# Non-Isolated_Interface.net
KiCad netlist of a schematic drawn in Altium Designer
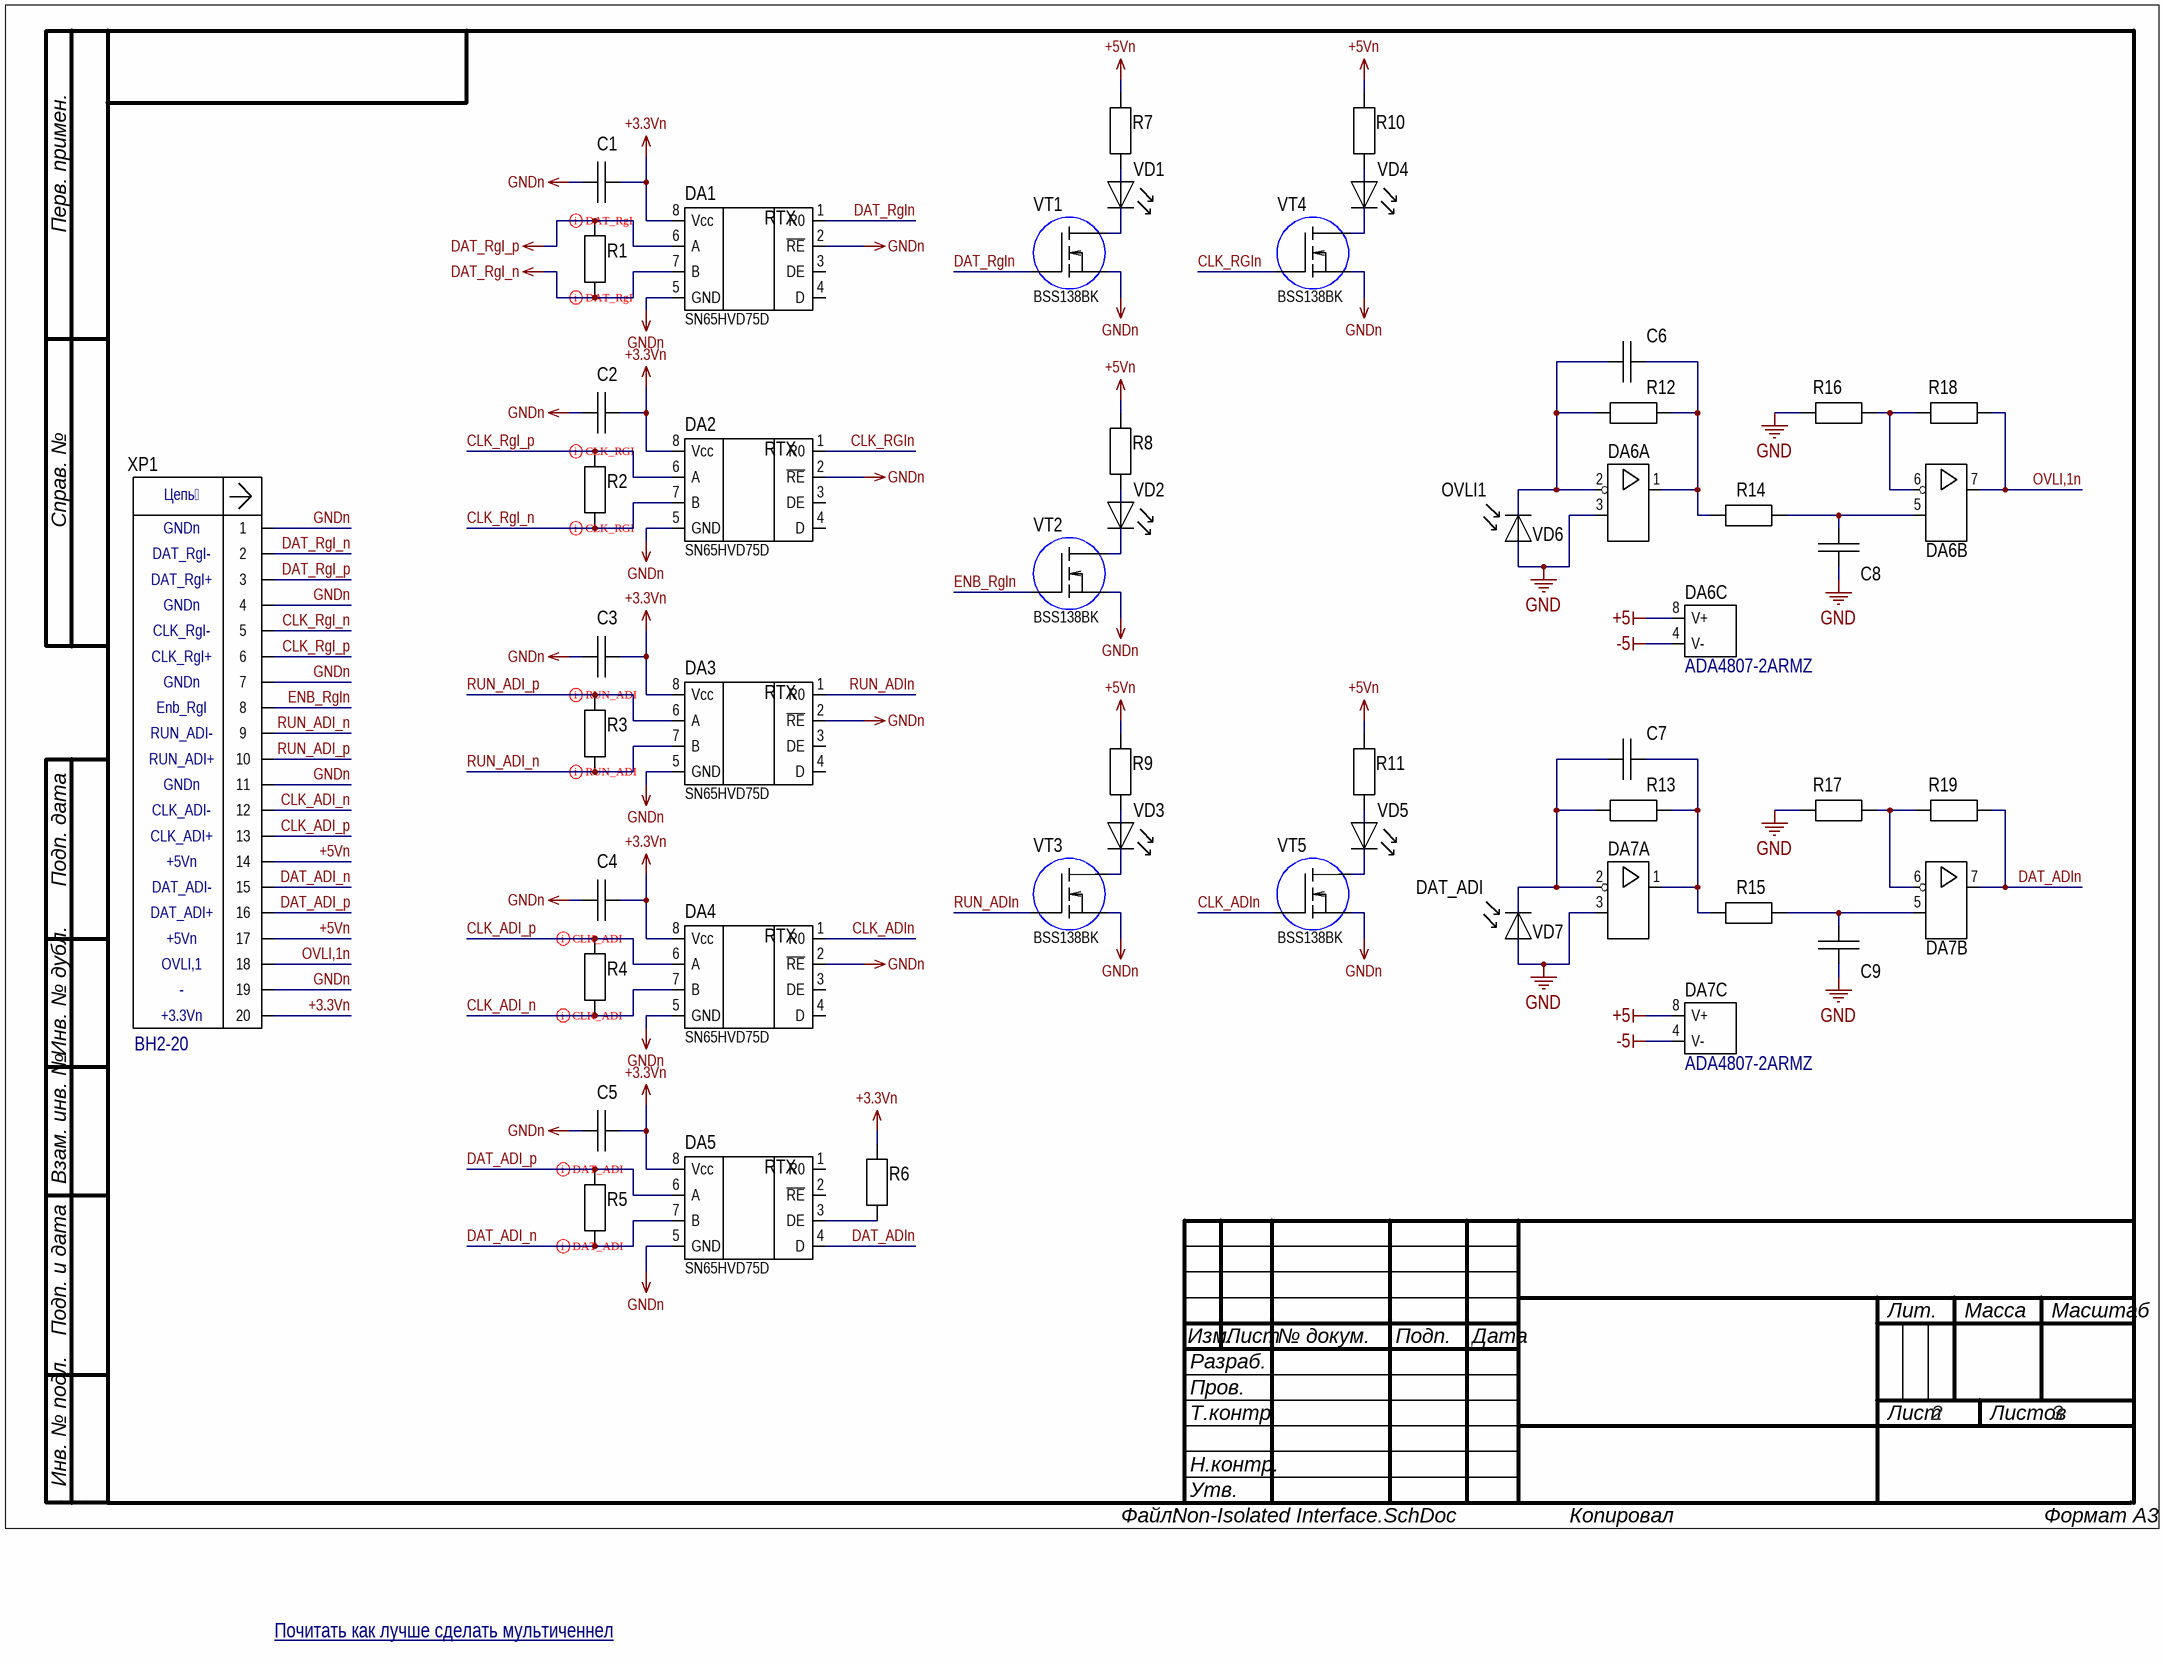
[diagram p0: Non-Isolated Interface.SchDoc]

(export (version "E")
  (design (tool "Eeschema 10.0.6"))
  (components
    (comp (ref "C1")
      (value "0805-X7R-25 В-0,1 мкФ +-10%")
      (footprint "standard-case:CAP: 0805")
      (libsource (lib "МНИПИ_Конденсаторы") (part "0805-X7R-25 В-0,1 мкФ +-10%"))
    )
    (comp (ref "C2")
      (value "0805-X7R-25 В-0,1 мкФ +-10%")
      (footprint "standard-case:CAP: 0805")
      (libsource (lib "МНИПИ_Конденсаторы") (part "0805-X7R-25 В-0,1 мкФ +-10%"))
    )
    (comp (ref "C3")
      (value "0805-X7R-25 В-0,1 мкФ +-10%")
      (footprint "standard-case:CAP: 0805")
      (libsource (lib "МНИПИ_Конденсаторы") (part "0805-X7R-25 В-0,1 мкФ +-10%"))
    )
    (comp (ref "C4")
      (value "0805-X7R-25 В-0,1 мкФ +-10%")
      (footprint "standard-case:CAP: 0805")
      (libsource (lib "МНИПИ_Конденсаторы") (part "0805-X7R-25 В-0,1 мкФ +-10%"))
    )
    (comp (ref "C5")
      (value "0805-X7R-25 В-0,1 мкФ +-10%")
      (footprint "standard-case:CAP: 0805")
      (libsource (lib "МНИПИ_Конденсаторы") (part "0805-X7R-25 В-0,1 мкФ +-10%"))
    )
    (comp (ref "C6")
      (value "0805-NP0-50 В-2,4 пФ-1%")
      (footprint "standard-case:CAP: 0805")
      (libsource (lib "МНИПИ_Конденсаторы") (part "0805-NP0-50 В-2,4 пФ-1%"))
    )
    (comp (ref "C7")
      (value "0805-NP0-50 В-2,4 пФ-1%")
      (footprint "standard-case:CAP: 0805")
      (libsource (lib "МНИПИ_Конденсаторы") (part "0805-NP0-50 В-2,4 пФ-1%"))
    )
    (comp (ref "C8")
      (value "1206-С0G-50 B-56 пФ+-1%")
      (footprint "standard-case:CAP: 1206")
      (libsource (lib "МНИПИ_Конденсаторы") (part "1206-С0G-50 B-56 пФ+-1%"))
    )
    (comp (ref "C9")
      (value "1206-С0G-50 B-56 пФ+-1%")
      (footprint "standard-case:CAP: 1206")
      (libsource (lib "МНИПИ_Конденсаторы") (part "1206-С0G-50 B-56 пФ+-1%"))
    )
    (comp (ref "DA1")
      (value "SN65HVD75D")
      (footprint "8-SOIC")
      (libsource (lib "МНИПИ_Микросхемы") (part "SN65HVD75D"))
    )
    (comp (ref "DA2")
      (value "SN65HVD75D")
      (footprint "8-SOIC")
      (libsource (lib "МНИПИ_Микросхемы") (part "SN65HVD75D"))
    )
    (comp (ref "DA3")
      (value "SN65HVD75D")
      (footprint "8-SOIC")
      (libsource (lib "МНИПИ_Микросхемы") (part "SN65HVD75D"))
    )
    (comp (ref "DA4")
      (value "SN65HVD75D")
      (footprint "8-SOIC")
      (libsource (lib "МНИПИ_Микросхемы") (part "SN65HVD75D"))
    )
    (comp (ref "DA5")
      (value "SN65HVD75D")
      (footprint "8-SOIC")
      (libsource (lib "МНИПИ_Микросхемы") (part "SN65HVD75D"))
    )
    (comp (ref "DA6")
      (value "ADA4807-2ARMZ")
      (footprint "8-MSOP")
      (description "3.1 nV/√Hz, 1 mA, 180 MHz,\r\nRail-to-Rail Input/Output Amplifiers")
      (libsource (lib "МНИПИ_Микросхемы") (part "ADA4807-2ARMZ"))
    )
    (comp (ref "DA7")
      (value "ADA4807-2ARMZ")
      (footprint "8-MSOP")
      (description "3.1 nV/√Hz, 1 mA, 180 MHz,\r\nRail-to-Rail Input/Output Amplifiers")
      (libsource (lib "МНИПИ_Микросхемы") (part "ADA4807-2ARMZ"))
    )
    (comp (ref "R1")
      (value "1206-100 Ом+-5%")
      (footprint "МНИПИ_Резисторы:1206")
      (libsource (lib "МНИПИ_Резисторы") (part "1206-100 Ом+-5%"))
    )
    (comp (ref "R2")
      (value "1206-100 Ом+-5%")
      (footprint "МНИПИ_Резисторы:1206")
      (libsource (lib "МНИПИ_Резисторы") (part "1206-100 Ом+-5%"))
    )
    (comp (ref "R3")
      (value "1206-100 Ом+-5%")
      (footprint "МНИПИ_Резисторы:1206")
      (libsource (lib "МНИПИ_Резисторы") (part "1206-100 Ом+-5%"))
    )
    (comp (ref "R4")
      (value "1206-100 Ом+-5%")
      (footprint "МНИПИ_Резисторы:1206")
      (libsource (lib "МНИПИ_Резисторы") (part "1206-100 Ом+-5%"))
    )
    (comp (ref "R5")
      (value "1206-100 Ом+-5%")
      (footprint "МНИПИ_Резисторы:1206")
      (libsource (lib "МНИПИ_Резисторы") (part "1206-100 Ом+-5%"))
    )
    (comp (ref "R6")
      (value "0805-10 KОМ+-5%")
      (footprint "МНИПИ_Резисторы:0805")
      (libsource (lib "МНИПИ_Резисторы") (part "0805-10 KОМ+-5%"))
    )
    (comp (ref "R7")
      (value "1206-30 Ом+-5%")
      (footprint "МНИПИ_Резисторы:1206")
      (libsource (lib "МНИПИ_Резисторы") (part "1206-30 Ом+-5%"))
    )
    (comp (ref "R8")
      (value "1206-30 Ом+-5%")
      (footprint "МНИПИ_Резисторы:1206")
      (libsource (lib "МНИПИ_Резисторы") (part "1206-30 Ом+-5%"))
    )
    (comp (ref "R9")
      (value "1206-30 Ом+-5%")
      (footprint "МНИПИ_Резисторы:1206")
      (libsource (lib "МНИПИ_Резисторы") (part "1206-30 Ом+-5%"))
    )
    (comp (ref "R10")
      (value "1206-30 Ом+-5%")
      (footprint "МНИПИ_Резисторы:1206")
      (libsource (lib "МНИПИ_Резисторы") (part "1206-30 Ом+-5%"))
    )
    (comp (ref "R11")
      (value "1206-30 Ом+-5%")
      (footprint "МНИПИ_Резисторы:1206")
      (libsource (lib "МНИПИ_Резисторы") (part "1206-30 Ом+-5%"))
    )
    (comp (ref "R12")
      (value "1206-5,23 кОм+-1%")
      (footprint "МНИПИ_Резисторы:1206")
      (libsource (lib "МНИПИ_Резисторы") (part "1206-5,23 кОм+-1%"))
    )
    (comp (ref "R13")
      (value "1206-5,23 кОм+-1%")
      (footprint "МНИПИ_Резисторы:1206")
      (libsource (lib "МНИПИ_Резисторы") (part "1206-5,23 кОм+-1%"))
    )
    (comp (ref "R14")
      (value "1206-140 Ом+-1%")
      (footprint "МНИПИ_Резисторы:1206")
      (libsource (lib "МНИПИ_Резисторы") (part "1206-140 Ом+-1%"))
    )
    (comp (ref "R15")
      (value "1206-140 Ом+-1%")
      (footprint "МНИПИ_Резисторы:1206")
      (libsource (lib "МНИПИ_Резисторы") (part "1206-140 Ом+-1%"))
    )
    (comp (ref "R16")
      (value "1206-102 Ом+-1%")
      (footprint "МНИПИ_Резисторы:1206")
      (libsource (lib "МНИПИ_Резисторы") (part "1206-102 Ом+-1%"))
    )
    (comp (ref "R17")
      (value "1206-102 Ом+-1%")
      (footprint "МНИПИ_Резисторы:1206")
      (libsource (lib "МНИПИ_Резисторы") (part "1206-102 Ом+-1%"))
    )
    (comp (ref "R18")
      (value "1206-215 Ом+-1%")
      (footprint "МНИПИ_Резисторы:1206")
      (libsource (lib "МНИПИ_Резисторы") (part "1206-215 Ом+-1%"))
    )
    (comp (ref "R19")
      (value "1206-215 Ом+-1%")
      (footprint "МНИПИ_Резисторы:1206")
      (libsource (lib "МНИПИ_Резисторы") (part "1206-215 Ом+-1%"))
    )
    (comp (ref "VD1")
      (value "VSMY2853RG")
      (footprint "VSMY2853G")
      (description "High Speed Infrared Emitting Diodes, 850 nm,\r\nSurface Emitter Technology")
      (libsource (lib "МНИПИ_Диоды") (part "VSMY2853RG"))
    )
    (comp (ref "VD2")
      (value "VSMY2853RG")
      (footprint "VSMY2853G")
      (description "High Speed Infrared Emitting Diodes, 850 nm,\r\nSurface Emitter Technology")
      (libsource (lib "МНИПИ_Диоды") (part "VSMY2853RG"))
    )
    (comp (ref "VD3")
      (value "VSMY2853RG")
      (footprint "VSMY2853G")
      (description "High Speed Infrared Emitting Diodes, 850 nm,\r\nSurface Emitter Technology")
      (libsource (lib "МНИПИ_Диоды") (part "VSMY2853RG"))
    )
    (comp (ref "VD4")
      (value "VSMY2853RG")
      (footprint "VSMY2853G")
      (description "High Speed Infrared Emitting Diodes, 850 nm,\r\nSurface Emitter Technology")
      (libsource (lib "МНИПИ_Диоды") (part "VSMY2853RG"))
    )
    (comp (ref "VD5")
      (value "VSMY2853RG")
      (footprint "VSMY2853G")
      (description "High Speed Infrared Emitting Diodes, 850 nm,\r\nSurface Emitter Technology")
      (libsource (lib "МНИПИ_Диоды") (part "VSMY2853RG"))
    )
    (comp (ref "VD6")
      (value "SFH203")
      (footprint "SFH203")
      (description "Silicon PIN Photodiode")
      (libsource (lib "МНИПИ_Диоды") (part "SFH203"))
    )
    (comp (ref "VD7")
      (value "SFH203")
      (footprint "SFH203")
      (description "Silicon PIN Photodiode")
      (libsource (lib "МНИПИ_Диоды") (part "SFH203"))
    )
    (comp (ref "VT1")
      (value "BSS138BK")
      (footprint "SOT-23-3")
      (description "60 V, 360 mA N-channel Trench MOSFET")
      (libsource (lib "МНИПИ_Транзисторы") (part "BSS138BK"))
    )
    (comp (ref "VT2")
      (value "BSS138BK")
      (footprint "SOT-23-3")
      (description "60 V, 360 mA N-channel Trench MOSFET")
      (libsource (lib "МНИПИ_Транзисторы") (part "BSS138BK"))
    )
    (comp (ref "VT3")
      (value "BSS138BK")
      (footprint "SOT-23-3")
      (description "60 V, 360 mA N-channel Trench MOSFET")
      (libsource (lib "МНИПИ_Транзисторы") (part "BSS138BK"))
    )
    (comp (ref "VT4")
      (value "BSS138BK")
      (footprint "SOT-23-3")
      (description "60 V, 360 mA N-channel Trench MOSFET")
      (libsource (lib "МНИПИ_Транзисторы") (part "BSS138BK"))
    )
    (comp (ref "VT5")
      (value "BSS138BK")
      (footprint "SOT-23-3")
      (description "60 V, 360 mA N-channel Trench MOSFET")
      (libsource (lib "МНИПИ_Транзисторы") (part "BSS138BK"))
    )
    (comp (ref "XP1")
      (value "BH2-20")
      (footprint "DS1014-20S")
      (description "pitch 2mm, 20 pin 2x10")
      (libsource (lib "МНИПИ_Разъемы") (part "BH2-20"))
    )
  )
  (nets
    (net (code "1") (name "+3.3Vn") (class "Default")
      (node (ref "C1") (pin "2") (pinfunction "2_2") (pintype "passive"))
      (node (ref "C2") (pin "2") (pinfunction "2_2") (pintype "passive"))
      (node (ref "C3") (pin "2") (pinfunction "2_2") (pintype "passive"))
      (node (ref "C4") (pin "2") (pinfunction "2_2") (pintype "passive"))
      (node (ref "C5") (pin "2") (pinfunction "2_2") (pintype "passive"))
      (node (ref "DA1") (pin "8") (pinfunction "Vcc_8") (pintype "passive"))
      (node (ref "DA2") (pin "8") (pinfunction "Vcc_8") (pintype "passive"))
      (node (ref "DA3") (pin "8") (pinfunction "Vcc_8") (pintype "passive"))
      (node (ref "DA4") (pin "8") (pinfunction "Vcc_8") (pintype "passive"))
      (node (ref "DA5") (pin "8") (pinfunction "Vcc_8") (pintype "passive"))
      (node (ref "R6") (pin "2") (pintype "passive"))
      (node (ref "XP1") (pin "20") (pinfunction "20_20") (pintype "passive"))
    )
    (net (code "2") (name "+5") (class "Default")
      (node (ref "DA6") (pin "8") (pinfunction "V+_8") (pintype "passive"))
      (node (ref "DA7") (pin "8") (pinfunction "V+_8") (pintype "passive"))
    )
    (net (code "3") (name "+5Vn") (class "Default")
      (node (ref "R10") (pin "2") (pinfunction "2_2") (pintype "passive"))
      (node (ref "R11") (pin "2") (pinfunction "2_2") (pintype "passive"))
      (node (ref "R7") (pin "2") (pinfunction "2_2") (pintype "passive"))
      (node (ref "R8") (pin "2") (pinfunction "2_2") (pintype "passive"))
      (node (ref "R9") (pin "2") (pinfunction "2_2") (pintype "passive"))
      (node (ref "XP1") (pin "14") (pinfunction "14_14") (pintype "passive"))
      (node (ref "XP1") (pin "17") (pinfunction "17_17") (pintype "passive"))
    )
    (net (code "4") (name "-5") (class "Default")
      (node (ref "DA6") (pin "4") (pinfunction "V-_4") (pintype "passive"))
      (node (ref "DA7") (pin "4") (pinfunction "V-_4") (pintype "passive"))
    )
    (net (code "5") (name "/CLK_ADI_n") (class "Default")
      (node (ref "DA4") (pin "7") (pinfunction "B_7") (pintype "passive"))
      (node (ref "R4") (pin "1") (pinfunction "1_1") (pintype "passive"))
      (node (ref "XP1") (pin "12") (pinfunction "12_12") (pintype "passive"))
    )
    (net (code "6") (name "/CLK_ADI_p") (class "Default")
      (node (ref "DA4") (pin "6") (pinfunction "A_6") (pintype "passive"))
      (node (ref "R4") (pin "2") (pinfunction "1_2") (pintype "passive"))
      (node (ref "XP1") (pin "13") (pinfunction "13_13") (pintype "passive"))
    )
    (net (code "7") (name "/CLK_ADIn") (class "Default")
      (node (ref "DA4") (pin "1") (pinfunction "R0_1") (pintype "passive"))
      (node (ref "VT5") (pin "1") (pinfunction "G_1") (pintype "passive"))
    )
    (net (code "8") (name "/CLK_RGIn") (class "Default")
      (node (ref "DA2") (pin "1") (pinfunction "R0_1") (pintype "passive"))
      (node (ref "VT4") (pin "1") (pinfunction "G_1") (pintype "passive"))
    )
    (net (code "9") (name "/CLK_RgI_n") (class "Default")
      (node (ref "DA2") (pin "7") (pinfunction "B_7") (pintype "passive"))
      (node (ref "R2") (pin "1") (pinfunction "1_1") (pintype "passive"))
      (node (ref "XP1") (pin "5") (pinfunction "5_5") (pintype "passive"))
    )
    (net (code "10") (name "/CLK_RgI_p") (class "Default")
      (node (ref "DA2") (pin "6") (pinfunction "A_6") (pintype "passive"))
      (node (ref "R2") (pin "2") (pinfunction "1_2") (pintype "passive"))
      (node (ref "XP1") (pin "6") (pinfunction "6_6") (pintype "passive"))
    )
    (net (code "11") (name "/DAT_ADI_n") (class "Default")
      (node (ref "DA5") (pin "7") (pinfunction "B_7") (pintype "passive"))
      (node (ref "R5") (pin "1") (pinfunction "1_1") (pintype "passive"))
      (node (ref "XP1") (pin "15") (pinfunction "15_15") (pintype "passive"))
    )
    (net (code "12") (name "/DAT_ADI_p") (class "Default")
      (node (ref "DA5") (pin "6") (pinfunction "A_6") (pintype "passive"))
      (node (ref "R5") (pin "2") (pinfunction "1_2") (pintype "passive"))
      (node (ref "XP1") (pin "16") (pinfunction "16_16") (pintype "passive"))
    )
    (net (code "13") (name "/DAT_ADIn") (class "Default")
      (node (ref "DA5") (pin "4") (pinfunction "D_4") (pintype "passive"))
      (node (ref "DA7") (pin "7") (pinfunction "OUT_B_7") (pintype "passive"))
      (node (ref "R19") (pin "2") (pinfunction "2_2") (pintype "passive"))
    )
    (net (code "14") (name "/DAT_RgIn") (class "Default")
      (node (ref "DA1") (pin "1") (pinfunction "R0_1") (pintype "passive"))
      (node (ref "VT1") (pin "1") (pinfunction "G_1") (pintype "passive"))
    )
    (net (code "15") (name "/ENB_RgIn") (class "Default")
      (node (ref "VT2") (pin "1") (pinfunction "G_1") (pintype "passive"))
      (node (ref "XP1") (pin "8") (pinfunction "8_8") (pintype "passive"))
    )
    (net (code "16") (name "/OVLI,1n") (class "Default")
      (node (ref "DA6") (pin "7") (pinfunction "OUT_B_7") (pintype "passive"))
      (node (ref "R18") (pin "2") (pinfunction "2_2") (pintype "passive"))
      (node (ref "XP1") (pin "18") (pinfunction "18_18") (pintype "passive"))
    )
    (net (code "17") (name "/RUN_ADI_n") (class "Default")
      (node (ref "DA3") (pin "7") (pinfunction "B_7") (pintype "passive"))
      (node (ref "R3") (pin "1") (pinfunction "1_1") (pintype "passive"))
      (node (ref "XP1") (pin "9") (pinfunction "9_9") (pintype "passive"))
    )
    (net (code "18") (name "/RUN_ADI_p") (class "Default")
      (node (ref "DA3") (pin "6") (pinfunction "A_6") (pintype "passive"))
      (node (ref "R3") (pin "2") (pinfunction "1_2") (pintype "passive"))
      (node (ref "XP1") (pin "10") (pinfunction "10_10") (pintype "passive"))
    )
    (net (code "19") (name "/RUN_ADIn") (class "Default")
      (node (ref "DA3") (pin "1") (pinfunction "R0_1") (pintype "passive"))
      (node (ref "VT3") (pin "1") (pinfunction "G_1") (pintype "passive"))
    )
    (net (code "20") (name "DAT_RgI_n") (class "Default")
      (node (ref "DA1") (pin "7") (pinfunction "B_7") (pintype "passive"))
      (node (ref "R1") (pin "1") (pinfunction "1_1") (pintype "passive"))
      (node (ref "XP1") (pin "2") (pinfunction "2_2") (pintype "passive"))
    )
    (net (code "21") (name "DAT_RgI_p") (class "Default")
      (node (ref "DA1") (pin "6") (pinfunction "A_6") (pintype "passive"))
      (node (ref "R1") (pin "2") (pinfunction "1_2") (pintype "passive"))
      (node (ref "XP1") (pin "3") (pinfunction "3_3") (pintype "passive"))
    )
    (net (code "22") (name "GND") (class "Default")
      (node (ref "C8") (pin "1") (pinfunction "1_1") (pintype "passive"))
      (node (ref "C9") (pin "1") (pinfunction "1_1") (pintype "passive"))
      (node (ref "DA6") (pin "3") (pinfunction "+IN_A_3") (pintype "passive"))
      (node (ref "DA7") (pin "3") (pinfunction "+IN_A_3") (pintype "passive"))
      (node (ref "R16") (pin "1") (pinfunction "1_1") (pintype "passive"))
      (node (ref "R17") (pin "1") (pinfunction "1_1") (pintype "passive"))
      (node (ref "VD6") (pin "1") (pintype "passive"))
      (node (ref "VD7") (pin "1") (pintype "passive"))
    )
    (net (code "23") (name "GNDn") (class "Default")
      (node (ref "C1") (pin "1") (pinfunction "1_1") (pintype "passive"))
      (node (ref "C2") (pin "1") (pinfunction "1_1") (pintype "passive"))
      (node (ref "C3") (pin "1") (pinfunction "1_1") (pintype "passive"))
      (node (ref "C4") (pin "1") (pinfunction "1_1") (pintype "passive"))
      (node (ref "C5") (pin "1") (pinfunction "1_1") (pintype "passive"))
      (node (ref "DA1") (pin "2") (pinfunction "RE_2") (pintype "passive"))
      (node (ref "DA1") (pin "5") (pinfunction "GND_5") (pintype "passive"))
      (node (ref "DA2") (pin "2") (pinfunction "RE_2") (pintype "passive"))
      (node (ref "DA2") (pin "5") (pinfunction "GND_5") (pintype "passive"))
      (node (ref "DA3") (pin "2") (pinfunction "RE_2") (pintype "passive"))
      (node (ref "DA3") (pin "5") (pinfunction "GND_5") (pintype "passive"))
      (node (ref "DA4") (pin "2") (pinfunction "RE_2") (pintype "passive"))
      (node (ref "DA4") (pin "5") (pinfunction "GND_5") (pintype "passive"))
      (node (ref "DA5") (pin "5") (pinfunction "GND_5") (pintype "passive"))
      (node (ref "VT1") (pin "2") (pinfunction "S_2") (pintype "passive"))
      (node (ref "VT2") (pin "2") (pinfunction "S_2") (pintype "passive"))
      (node (ref "VT3") (pin "2") (pinfunction "S_2") (pintype "passive"))
      (node (ref "VT4") (pin "2") (pinfunction "S_2") (pintype "passive"))
      (node (ref "VT5") (pin "2") (pinfunction "S_2") (pintype "passive"))
      (node (ref "XP1") (pin "1") (pinfunction "1_1") (pintype "passive"))
      (node (ref "XP1") (pin "11") (pinfunction "11_11") (pintype "passive"))
      (node (ref "XP1") (pin "19") (pinfunction "19_19") (pintype "passive"))
      (node (ref "XP1") (pin "4") (pinfunction "4_4") (pintype "passive"))
      (node (ref "XP1") (pin "7") (pinfunction "7_7") (pintype "passive"))
    )
    (net (code "24") (name "Net-(DA5-DE)") (class "Default")
      (node (ref "DA5") (pin "3") (pinfunction "DE_3") (pintype "passive"))
      (node (ref "R6") (pin "1") (pintype "passive"))
    )
    (net (code "25") (name "Net-(DA6A--IN_A)") (class "Default")
      (node (ref "C6") (pin "1") (pinfunction "1_1") (pintype "passive"))
      (node (ref "DA6") (pin "2") (pinfunction "-IN_A_2") (pintype "passive"))
      (node (ref "R12") (pin "1") (pinfunction "1_1") (pintype "passive"))
      (node (ref "VD6") (pin "2") (pintype "passive"))
    )
    (net (code "26") (name "Net-(DA6A-OUT_A)") (class "Default")
      (node (ref "C6") (pin "2") (pinfunction "2_2") (pintype "passive"))
      (node (ref "DA6") (pin "1") (pinfunction "OUT_A_1") (pintype "passive"))
      (node (ref "R12") (pin "2") (pinfunction "2_2") (pintype "passive"))
      (node (ref "R14") (pin "1") (pinfunction "1_1") (pintype "passive"))
    )
    (net (code "27") (name "Net-(DA6B-+IN_B)") (class "Default")
      (node (ref "C8") (pin "2") (pinfunction "2_2") (pintype "passive"))
      (node (ref "DA6") (pin "5") (pinfunction "+IN_B_5") (pintype "passive"))
      (node (ref "R14") (pin "2") (pinfunction "2_2") (pintype "passive"))
    )
    (net (code "28") (name "Net-(DA6B--IN_B)") (class "Default")
      (node (ref "DA6") (pin "6") (pinfunction "-IN_B_6") (pintype "passive"))
      (node (ref "R16") (pin "2") (pinfunction "2_2") (pintype "passive"))
      (node (ref "R18") (pin "1") (pinfunction "1_1") (pintype "passive"))
    )
    (net (code "29") (name "Net-(DA7A--IN_A)") (class "Default")
      (node (ref "C7") (pin "1") (pinfunction "1_1") (pintype "passive"))
      (node (ref "DA7") (pin "2") (pinfunction "-IN_A_2") (pintype "passive"))
      (node (ref "R13") (pin "1") (pinfunction "1_1") (pintype "passive"))
      (node (ref "VD7") (pin "2") (pintype "passive"))
    )
    (net (code "30") (name "Net-(DA7A-OUT_A)") (class "Default")
      (node (ref "C7") (pin "2") (pinfunction "2_2") (pintype "passive"))
      (node (ref "DA7") (pin "1") (pinfunction "OUT_A_1") (pintype "passive"))
      (node (ref "R13") (pin "2") (pinfunction "2_2") (pintype "passive"))
      (node (ref "R15") (pin "1") (pinfunction "1_1") (pintype "passive"))
    )
    (net (code "31") (name "Net-(DA7B-+IN_B)") (class "Default")
      (node (ref "C9") (pin "2") (pinfunction "2_2") (pintype "passive"))
      (node (ref "DA7") (pin "5") (pinfunction "+IN_B_5") (pintype "passive"))
      (node (ref "R15") (pin "2") (pinfunction "2_2") (pintype "passive"))
    )
    (net (code "32") (name "Net-(DA7B--IN_B)") (class "Default")
      (node (ref "DA7") (pin "6") (pinfunction "-IN_B_6") (pintype "passive"))
      (node (ref "R17") (pin "2") (pinfunction "2_2") (pintype "passive"))
      (node (ref "R19") (pin "1") (pinfunction "1_1") (pintype "passive"))
    )
    (net (code "33") (name "Net-(VD1-Anode)") (class "Default")
      (node (ref "R7") (pin "1") (pinfunction "1_1") (pintype "passive"))
      (node (ref "VD1") (pin "1") (pinfunction "Anode_1") (pintype "passive"))
    )
    (net (code "34") (name "Net-(VD1-Cathode)") (class "Default")
      (node (ref "VD1") (pin "2") (pinfunction "Cathode_2") (pintype "passive"))
      (node (ref "VT1") (pin "3") (pinfunction "D_3") (pintype "passive"))
    )
    (net (code "35") (name "Net-(VD2-Anode)") (class "Default")
      (node (ref "R8") (pin "1") (pinfunction "1_1") (pintype "passive"))
      (node (ref "VD2") (pin "1") (pinfunction "Anode_1") (pintype "passive"))
    )
    (net (code "36") (name "Net-(VD2-Cathode)") (class "Default")
      (node (ref "VD2") (pin "2") (pinfunction "Cathode_2") (pintype "passive"))
      (node (ref "VT2") (pin "3") (pinfunction "D_3") (pintype "passive"))
    )
    (net (code "37") (name "Net-(VD3-Anode)") (class "Default")
      (node (ref "R9") (pin "1") (pinfunction "1_1") (pintype "passive"))
      (node (ref "VD3") (pin "1") (pinfunction "Anode_1") (pintype "passive"))
    )
    (net (code "38") (name "Net-(VD3-Cathode)") (class "Default")
      (node (ref "VD3") (pin "2") (pinfunction "Cathode_2") (pintype "passive"))
      (node (ref "VT3") (pin "3") (pinfunction "D_3") (pintype "passive"))
    )
    (net (code "39") (name "Net-(VD4-Anode)") (class "Default")
      (node (ref "R10") (pin "1") (pinfunction "1_1") (pintype "passive"))
      (node (ref "VD4") (pin "1") (pinfunction "Anode_1") (pintype "passive"))
    )
    (net (code "40") (name "Net-(VD4-Cathode)") (class "Default")
      (node (ref "VD4") (pin "2") (pinfunction "Cathode_2") (pintype "passive"))
      (node (ref "VT4") (pin "3") (pinfunction "D_3") (pintype "passive"))
    )
    (net (code "41") (name "Net-(VD5-Anode)") (class "Default")
      (node (ref "R11") (pin "1") (pinfunction "1_1") (pintype "passive"))
      (node (ref "VD5") (pin "1") (pinfunction "Anode_1") (pintype "passive"))
    )
    (net (code "42") (name "Net-(VD5-Cathode)") (class "Default")
      (node (ref "VD5") (pin "2") (pinfunction "Cathode_2") (pintype "passive"))
      (node (ref "VT5") (pin "3") (pinfunction "D_3") (pintype "passive"))
    )
    (net (code "43") (name "unconnected-(DA1-D-Pad4)") (class "Default")
      (node (ref "DA1") (pin "4") (pinfunction "D_4") (pintype "passive"))
    )
    (net (code "44") (name "unconnected-(DA1-DE-Pad3)") (class "Default")
      (node (ref "DA1") (pin "3") (pinfunction "DE_3") (pintype "passive"))
    )
    (net (code "45") (name "unconnected-(DA2-D-Pad4)") (class "Default")
      (node (ref "DA2") (pin "4") (pinfunction "D_4") (pintype "passive"))
    )
    (net (code "46") (name "unconnected-(DA2-DE-Pad3)") (class "Default")
      (node (ref "DA2") (pin "3") (pinfunction "DE_3") (pintype "passive"))
    )
    (net (code "47") (name "unconnected-(DA3-D-Pad4)") (class "Default")
      (node (ref "DA3") (pin "4") (pinfunction "D_4") (pintype "passive"))
    )
    (net (code "48") (name "unconnected-(DA3-DE-Pad3)") (class "Default")
      (node (ref "DA3") (pin "3") (pinfunction "DE_3") (pintype "passive"))
    )
    (net (code "49") (name "unconnected-(DA4-D-Pad4)") (class "Default")
      (node (ref "DA4") (pin "4") (pinfunction "D_4") (pintype "passive"))
    )
    (net (code "50") (name "unconnected-(DA4-DE-Pad3)") (class "Default")
      (node (ref "DA4") (pin "3") (pinfunction "DE_3") (pintype "passive"))
    )
    (net (code "51") (name "unconnected-(DA5-R0-Pad1)") (class "Default")
      (node (ref "DA5") (pin "1") (pinfunction "R0_1") (pintype "passive"))
    )
    (net (code "52") (name "unconnected-(DA5-RE-Pad2)") (class "Default")
      (node (ref "DA5") (pin "2") (pinfunction "RE_2") (pintype "passive"))
    )
  )
)
